# digital_host_for_ADS1216_power.net
KiCad netlist of a schematic drawn in Altium Designer
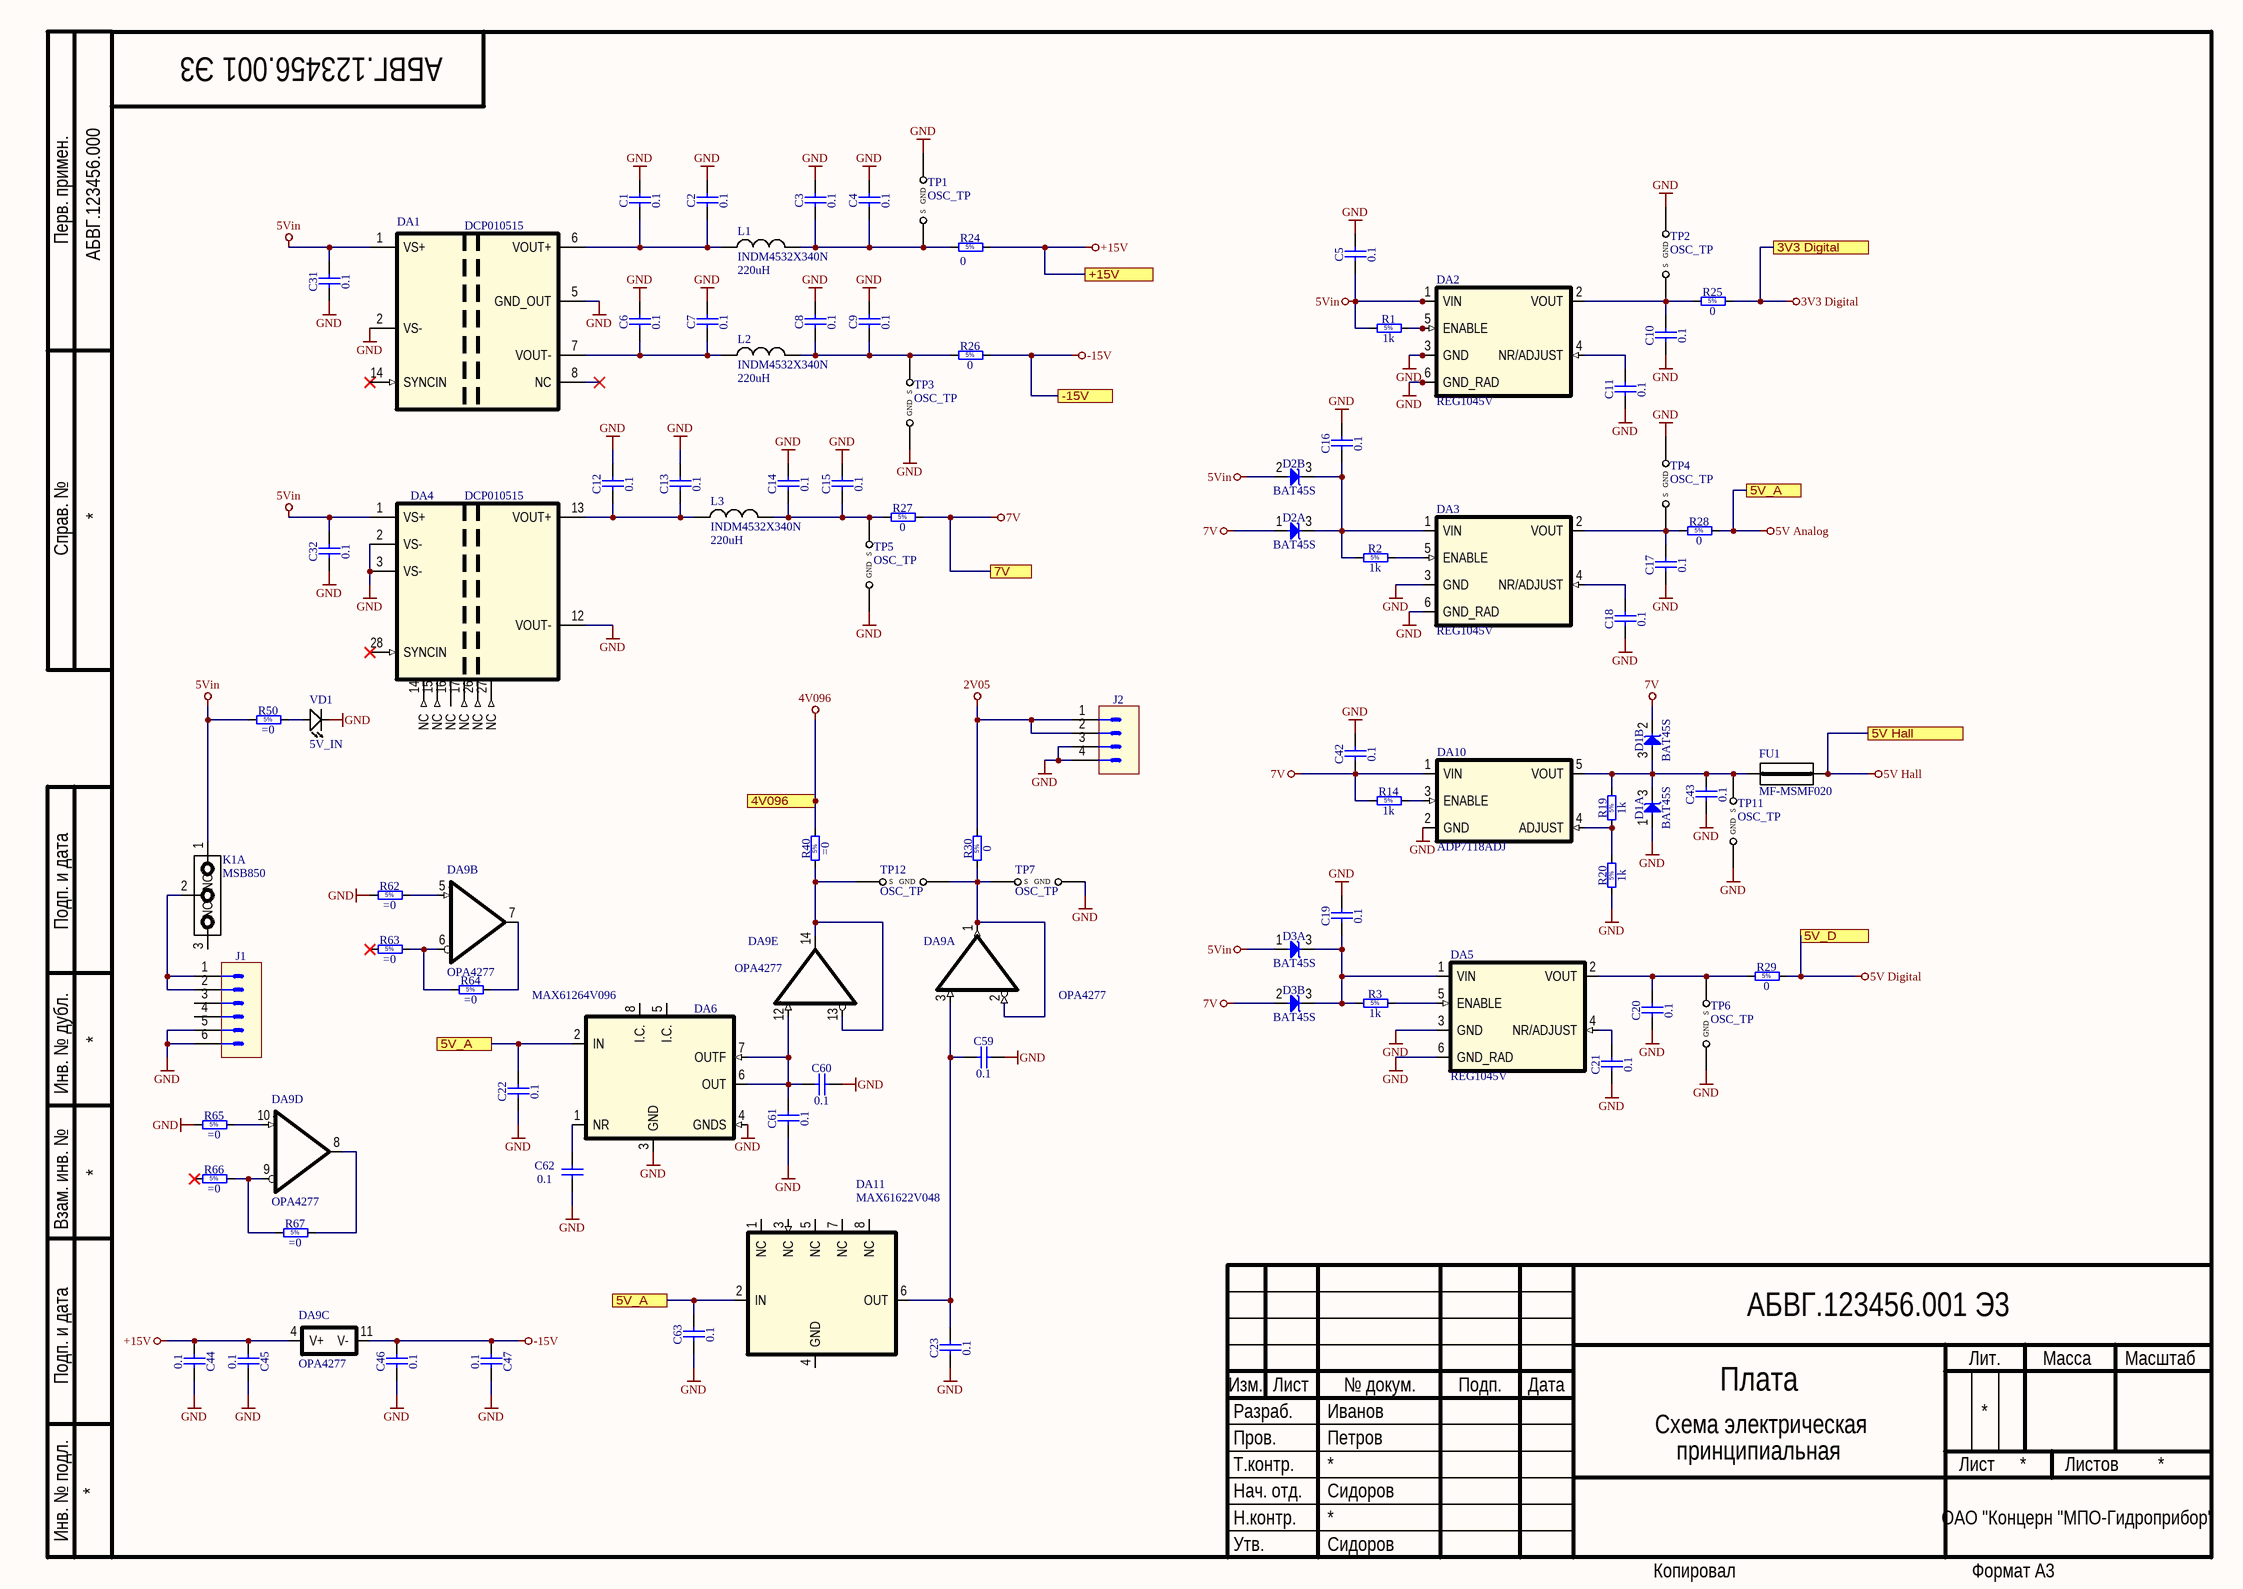
[diagram p0: digital_host_for_ADS1216_power.SchDoc]

(export (version "E")
  (design (tool "Eeschema 10.0.6"))
  (components
    (comp (ref "C1")
      (value "0.1")
      (footprint "CAPC2012X90N")
      (description "Non-polarised capacitor2012")
      (libsource (lib "schematic_hall_library") (part "Capacitor - non polarized"))
    )
    (comp (ref "C2")
      (value "0.1")
      (footprint "CAPC2012X90N")
      (description "Non-polarised capacitor2012")
      (libsource (lib "schematic_hall_library") (part "Capacitor - non polarized"))
    )
    (comp (ref "C3")
      (value "0.1")
      (footprint "CAPC2012X90N")
      (description "Non-polarised capacitor2012")
      (libsource (lib "schematic_hall_library") (part "Capacitor - non polarized"))
    )
    (comp (ref "C4")
      (value "0.1")
      (footprint "CAPC2012X90N")
      (description "Non-polarised capacitor2012")
      (libsource (lib "schematic_hall_library") (part "Capacitor - non polarized"))
    )
    (comp (ref "C5")
      (value "0.1")
      (footprint "CAPC2012X90N")
      (description "Non-polarised capacitor2012")
      (libsource (lib "schematic_hall_library") (part "Capacitor - non polarized"))
    )
    (comp (ref "C6")
      (value "0.1")
      (footprint "CAPC2012X90N")
      (description "Non-polarised capacitor2012")
      (libsource (lib "schematic_hall_library") (part "Capacitor - non polarized"))
    )
    (comp (ref "C7")
      (value "0.1")
      (footprint "CAPC2012X90N")
      (description "Non-polarised capacitor2012")
      (libsource (lib "schematic_hall_library") (part "Capacitor - non polarized"))
    )
    (comp (ref "C8")
      (value "0.1")
      (footprint "CAPC2012X90N")
      (description "Non-polarised capacitor2012")
      (libsource (lib "schematic_hall_library") (part "Capacitor - non polarized"))
    )
    (comp (ref "C9")
      (value "0.1")
      (footprint "CAPC2012X90N")
      (description "Non-polarised capacitor2012")
      (libsource (lib "schematic_hall_library") (part "Capacitor - non polarized"))
    )
    (comp (ref "C10")
      (value "0.1")
      (footprint "CAPC2012X90N")
      (description "Non-polarised capacitor2012")
      (libsource (lib "schematic_hall_library") (part "Capacitor - non polarized"))
    )
    (comp (ref "C11")
      (value "0.1")
      (footprint "CAPC2012X90N")
      (description "Non-polarised capacitor2012")
      (libsource (lib "schematic_hall_library") (part "Capacitor - non polarized"))
    )
    (comp (ref "C12")
      (value "0.1")
      (footprint "CAPC2012X90N")
      (description "Non-polarised capacitor2012")
      (libsource (lib "schematic_hall_library") (part "Capacitor - non polarized"))
    )
    (comp (ref "C13")
      (value "0.1")
      (footprint "CAPC2012X90N")
      (description "Non-polarised capacitor2012")
      (libsource (lib "schematic_hall_library") (part "Capacitor - non polarized"))
    )
    (comp (ref "C14")
      (value "0.1")
      (footprint "CAPC2012X90N")
      (description "Non-polarised capacitor2012")
      (libsource (lib "schematic_hall_library") (part "Capacitor - non polarized"))
    )
    (comp (ref "C15")
      (value "0.1")
      (footprint "CAPC2012X90N")
      (description "Non-polarised capacitor2012")
      (libsource (lib "schematic_hall_library") (part "Capacitor - non polarized"))
    )
    (comp (ref "C16")
      (value "0.1")
      (footprint "CAPC2012X90N")
      (description "Non-polarised capacitor2012")
      (libsource (lib "schematic_hall_library") (part "Capacitor - non polarized"))
    )
    (comp (ref "C17")
      (value "0.1")
      (footprint "CAPC2012X90N")
      (description "Non-polarised capacitor2012")
      (libsource (lib "schematic_hall_library") (part "Capacitor - non polarized"))
    )
    (comp (ref "C18")
      (value "0.1")
      (footprint "CAPC2012X90N")
      (description "Non-polarised capacitor2012")
      (libsource (lib "schematic_hall_library") (part "Capacitor - non polarized"))
    )
    (comp (ref "C19")
      (value "0.1")
      (footprint "CAPC2012X90N")
      (description "Non-polarised capacitor2012")
      (libsource (lib "schematic_hall_library") (part "Capacitor - non polarized"))
    )
    (comp (ref "C20")
      (value "0.1")
      (footprint "CAPC2012X90N")
      (description "Non-polarised capacitor2012")
      (libsource (lib "schematic_hall_library") (part "Capacitor - non polarized"))
    )
    (comp (ref "C21")
      (value "0.1")
      (footprint "CAPC2012X90N")
      (description "Non-polarised capacitor2012")
      (libsource (lib "schematic_hall_library") (part "Capacitor - non polarized"))
    )
    (comp (ref "C22")
      (value "0.1")
      (footprint "CAPC2012X90N")
      (description "Non-polarised capacitor2012")
      (libsource (lib "schematic_hall_library") (part "Capacitor - non polarized"))
    )
    (comp (ref "C23")
      (value "0.1")
      (footprint "CAPC2012X90N")
      (description "Non-polarised capacitor2012")
      (libsource (lib "schematic_hall_library") (part "Capacitor - non polarized"))
    )
    (comp (ref "C31")
      (value "0.1")
      (footprint "CAPC2012X90N")
      (description "Non-polarised capacitor2012")
      (libsource (lib "schematic_hall_library") (part "Capacitor - non polarized"))
    )
    (comp (ref "C32")
      (value "0.1")
      (footprint "CAPC2012X90N")
      (description "Non-polarised capacitor2012")
      (libsource (lib "schematic_hall_library") (part "Capacitor - non polarized"))
    )
    (comp (ref "C42")
      (value "0.1")
      (footprint "CAPC2012X90N")
      (description "Non-polarised capacitor2012")
      (libsource (lib "schematic_hall_library") (part "Capacitor - non polarized"))
    )
    (comp (ref "C43")
      (value "0.1")
      (footprint "CAPC2012X90N")
      (description "Non-polarised capacitor2012")
      (libsource (lib "schematic_hall_library") (part "Capacitor - non polarized"))
    )
    (comp (ref "C44")
      (value "0.1")
      (footprint "CAPC2012X90N")
      (description "Non-polarised capacitor2012")
      (libsource (lib "schematic_hall_library") (part "Capacitor - non polarized"))
    )
    (comp (ref "C45")
      (value "0.1")
      (footprint "CAPC2012X90N")
      (description "Non-polarised capacitor2012")
      (libsource (lib "schematic_hall_library") (part "Capacitor - non polarized"))
    )
    (comp (ref "C46")
      (value "0.1")
      (footprint "CAPC2012X90N")
      (description "Non-polarised capacitor2012")
      (libsource (lib "schematic_hall_library") (part "Capacitor - non polarized"))
    )
    (comp (ref "C47")
      (value "0.1")
      (footprint "CAPC2012X90N")
      (description "Non-polarised capacitor2012")
      (libsource (lib "schematic_hall_library") (part "Capacitor - non polarized"))
    )
    (comp (ref "C59")
      (value "0.1")
      (footprint "CAPC2012X90N")
      (description "Non-polarised capacitor2012")
      (libsource (lib "schematic_hall_library") (part "Capacitor - non polarized"))
    )
    (comp (ref "C60")
      (value "0.1")
      (footprint "CAPC2012X90N")
      (description "Non-polarised capacitor2012")
      (libsource (lib "schematic_hall_library") (part "Capacitor - non polarized"))
    )
    (comp (ref "C61")
      (value "0.1")
      (footprint "CAPC2012X90N")
      (description "Non-polarised capacitor2012")
      (libsource (lib "schematic_hall_library") (part "Capacitor - non polarized"))
    )
    (comp (ref "C62")
      (value "0.1")
      (footprint "CAPC2012X90N")
      (description "Non-polarised capacitor2012")
      (libsource (lib "schematic_hall_library") (part "Capacitor - non polarized"))
    )
    (comp (ref "C63")
      (value "0.1")
      (footprint "CAPC2012X90N")
      (description "Non-polarised capacitor2012")
      (libsource (lib "schematic_hall_library") (part "Capacitor - non polarized"))
    )
    (comp (ref "D1")
      (value "BAT45S")
      (footprint "footprint_library:SOT-23")
      (description "Serial Shottky Diode")
      (libsource (lib "first_scheme.~(65)") (part "BAT54S"))
    )
    (comp (ref "D2")
      (value "BAT45S")
      (footprint "SOT-23")
      (description "Common Cathode 2 Shottky Diode")
      (libsource (lib "Integrated_Library1") (part "BAT54C"))
    )
    (comp (ref "D3")
      (value "BAT45S")
      (footprint "SOT-23")
      (description "Common Cathode 2 Shottky Diode")
      (libsource (lib "Integrated_Library1") (part "BAT54C"))
    )
    (comp (ref "DA1")
      (value "DCP010515")
      (footprint "NVA7")
      (description "DC/DC 5V to isolated +-15V")
      (fields (field (name "COPYRIGHT") "Copyright (C) 2022 Ultra Librarian. All rights reserved."))
      (libsource (lib "Integrated_Library1") (part "DCP020515"))
    )
    (comp (ref "DA2")
      (value "REG1045V")
      (footprint "SOT223_6-127")
      (description "Positive LDO Linear stabilizer 5Vin to 3V3Digital")
      (libsource (lib "first_scheme.~(65)") (part "REG104_5V"))
    )
    (comp (ref "DA3")
      (value "REG1045V")
      (footprint "SOT223_6-127")
      (description "Positive LDO Linear stabilizer 7V to 5V Analog")
      (libsource (lib "first_scheme.~(65)") (part "REG104_5V"))
    )
    (comp (ref "DA4")
      (value "DCP010515")
      (footprint "footprint_library:SOIC127P1033X265-12_28N")
      (description "DC/DC 5V to isolated +-7V")
      (fields (field (name "COPYRIGHT") "Copyright (C) 2022 Ultra Librarian. All rights reserved."))
      (libsource (lib "first_scheme.~(65)") (part "DCP020507U"))
    )
    (comp (ref "DA5")
      (value "REG1045V")
      (footprint "SOT223_6-127")
      (description "Positive LDO Linear stabilizer 7V to 5V Digital")
      (libsource (lib "first_scheme.~(65)") (part "REG104_5V"))
    )
    (comp (ref "DA6")
      (value "MAX61264V096")
      (footprint "SO8")
      (description "Positive LDO Linear stabilizer")
      (libsource (lib "hall library") (part "MAX6126"))
    )
    (comp (ref "DA9")
      (value "OPA4277")
      (footprint "SOIC14")
      (description "счетверённый ОУ")
      (fields (field (name "VOLTAGE") "3..30V/+-1.5..+-15V"))
      (libsource (lib "Integrated_Library1") (part "OPA4277"))
    )
    (comp (ref "DA10")
      (value "ADP7118ADJ")
      (footprint "SOT95P270X145-5N")
      (description "Positive LDO Linear stabilizer")
      (libsource (lib "Integrated_Library1") (part "ADP7118"))
    )
    (comp (ref "DA11")
      (value "MAX61622V048")
      (footprint "SO8")
      (description "Reference LDO Linear stabilizer")
      (libsource (lib "hall library") (part "MAX6162"))
    )
    (comp (ref "FU1")
      (value "MF-MSMF020")
      (footprint "MSMF020")
      (description "Предохранитель самовосстанавливающийся")
      (libsource (lib "Integrated_Library1") (part "MF-MSMF"))
    )
    (comp (ref "J1")
      (value "~")
      (footprint "MOLEX_22-27-2061")
      (description "Connector 4 Male")
      (libsource (lib "hall library") (part "WF6"))
    )
    (comp (ref "J2")
      (value "~")
      (footprint "MOLEX_22-27-2041")
      (description "Connector 4 Male")
      (libsource (lib "hall library") (part "WF4"))
    )
    (comp (ref "K1")
      (value "MSB850")
      (footprint "MSB850")
      (description "Кнопка с фиксацией 2xSPDT")
      (libsource (lib "hall library") (part "MSB850"))
    )
    (comp (ref "L1")
      (value "INDM4532X340N")
      (footprint "footprint_library:INDM4532X340N")
      (description "SMD Дроссель")
      (fields (field (name "INDUCTANCE") "220uH"))
      (libsource (lib "first_scheme.~(65)") (part "INDM4532X340N"))
    )
    (comp (ref "L2")
      (value "INDM4532X340N")
      (footprint "footprint_library:INDM4532X340N")
      (description "SMD Дроссель")
      (fields (field (name "INDUCTANCE") "220uH"))
      (libsource (lib "first_scheme.~(65)") (part "INDM4532X340N"))
    )
    (comp (ref "L3")
      (value "INDM4532X340N")
      (footprint "footprint_library:INDM4532X340N")
      (description "SMD Дроссель")
      (fields (field (name "INDUCTANCE") "220uH"))
      (libsource (lib "first_scheme.~(65)") (part "INDM4532X340N"))
    )
    (comp (ref "R1")
      (value "1k")
      (footprint "RESC2012X70N")
      (description "Resistor - 5%")
      (fields (field (name "TOLERANCE") "5%"))
      (libsource (lib "first_scheme.~(65)") (part "Resistor - 5%"))
    )
    (comp (ref "R2")
      (value "1k")
      (footprint "RESC2012X70N")
      (description "Resistor - 5%")
      (fields (field (name "TOLERANCE") "5%"))
      (libsource (lib "first_scheme.~(65)") (part "Resistor - 5%"))
    )
    (comp (ref "R3")
      (value "1k")
      (footprint "RESC2012X70N")
      (description "Resistor - 5%")
      (fields (field (name "TOLERANCE") "5%"))
      (libsource (lib "first_scheme.~(65)") (part "Resistor - 5%"))
    )
    (comp (ref "R14")
      (value "1k")
      (footprint "RESC2012X70N")
      (description "Resistor - 5%")
      (fields (field (name "TOLERANCE") "5%"))
      (libsource (lib "Integrated_Library1") (part "Resistor - 5%"))
    )
    (comp (ref "R19")
      (value "1k")
      (footprint "RESC2012X70N")
      (description "Resistor - 5%")
      (fields (field (name "TOLERANCE") "5%"))
      (libsource (lib "Integrated_Library1") (part "Resistor - 5%"))
    )
    (comp (ref "R20")
      (value "1k")
      (footprint "RESC2012X70N")
      (description "Resistor - 5%")
      (fields (field (name "TOLERANCE") "5%"))
      (libsource (lib "Integrated_Library1") (part "Resistor - 5%"))
    )
    (comp (ref "R24")
      (value "0")
      (footprint "RESC2012X70N")
      (description "Resistor - 5%")
      (fields (field (name "TOLERANCE") "5%"))
      (libsource (lib "Integrated_Library1") (part "Resistor - 5%"))
    )
    (comp (ref "R25")
      (value "0")
      (footprint "RESC2012X70N")
      (description "Resistor - 5%")
      (fields (field (name "TOLERANCE") "5%"))
      (libsource (lib "Integrated_Library1") (part "Resistor - 5%"))
    )
    (comp (ref "R26")
      (value "0")
      (footprint "RESC2012X70N")
      (description "Resistor - 5%")
      (fields (field (name "TOLERANCE") "5%"))
      (libsource (lib "Integrated_Library1") (part "Resistor - 5%"))
    )
    (comp (ref "R27")
      (value "0")
      (footprint "RESC2012X70N")
      (description "Resistor - 5%")
      (fields (field (name "TOLERANCE") "5%"))
      (libsource (lib "Integrated_Library1") (part "Resistor - 5%"))
    )
    (comp (ref "R28")
      (value "0")
      (footprint "RESC2012X70N")
      (description "Resistor - 5%")
      (fields (field (name "TOLERANCE") "5%"))
      (libsource (lib "Integrated_Library1") (part "Resistor - 5%"))
    )
    (comp (ref "R29")
      (value "0")
      (footprint "RESC2012X70N")
      (description "Resistor - 5%")
      (fields (field (name "TOLERANCE") "5%"))
      (libsource (lib "Integrated_Library1") (part "Resistor - 5%"))
    )
    (comp (ref "R30")
      (value "0")
      (footprint "RESC2012X70N")
      (description "Resistor - 5%")
      (fields (field (name "TOLERANCE") "5%"))
      (libsource (lib "Integrated_Library1") (part "Resistor - 5%"))
    )
    (comp (ref "R40")
      (value "~")
      (footprint "RESC2012X70N")
      (description "Resistor - 5%")
      (fields (field (name "TOLERANCE") "5%"))
      (libsource (lib "Integrated_Library1") (part "Resistor - 5%"))
    )
    (comp (ref "R50")
      (value "~")
      (footprint "RESC2012X70N")
      (description "Resistor - 5%")
      (fields (field (name "TOLERANCE") "5%"))
      (libsource (lib "Integrated_Library1") (part "Resistor - 5%"))
    )
    (comp (ref "R62")
      (value "~")
      (footprint "RESC2012X70N")
      (description "Resistor - 5%")
      (fields (field (name "TOLERANCE") "5%"))
      (libsource (lib "Integrated_Library1") (part "Resistor - 5%"))
    )
    (comp (ref "R63")
      (value "~")
      (footprint "RESC2012X70N")
      (description "Resistor - 5%")
      (fields (field (name "TOLERANCE") "5%"))
      (libsource (lib "Integrated_Library1") (part "Resistor - 5%"))
    )
    (comp (ref "R64")
      (value "~")
      (footprint "RESC2012X70N")
      (description "Resistor - 5%")
      (fields (field (name "TOLERANCE") "5%"))
      (libsource (lib "Integrated_Library1") (part "Resistor - 5%"))
    )
    (comp (ref "R65")
      (value "~")
      (footprint "RESC2012X70N")
      (description "Resistor - 5%")
      (fields (field (name "TOLERANCE") "5%"))
      (libsource (lib "Integrated_Library1") (part "Resistor - 5%"))
    )
    (comp (ref "R66")
      (value "~")
      (footprint "RESC2012X70N")
      (description "Resistor - 5%")
      (fields (field (name "TOLERANCE") "5%"))
      (libsource (lib "Integrated_Library1") (part "Resistor - 5%"))
    )
    (comp (ref "R67")
      (value "~")
      (footprint "RESC2012X70N")
      (description "Resistor - 5%")
      (fields (field (name "TOLERANCE") "5%"))
      (libsource (lib "Integrated_Library1") (part "Resistor - 5%"))
    )
    (comp (ref "TP1")
      (value "OSC_TP")
      (footprint "footprint_library:TP2")
      (description "Контрольная точка для подключения осциллографа короткой землёй")
      (libsource (lib "first_scheme.~(65)") (part "OscTP"))
    )
    (comp (ref "TP2")
      (value "OSC_TP")
      (footprint "footprint_library:TP2")
      (description "Контрольная точка для подключения осциллографа короткой землёй")
      (libsource (lib "first_scheme.~(65)") (part "OscTP"))
    )
    (comp (ref "TP3")
      (value "OSC_TP")
      (footprint "footprint_library:TP2")
      (description "Контрольная точка для подключения осциллографа короткой землёй")
      (libsource (lib "first_scheme.~(65)") (part "OscTP"))
    )
    (comp (ref "TP4")
      (value "OSC_TP")
      (footprint "footprint_library:TP2")
      (description "Контрольная точка для подключения осциллографа короткой землёй")
      (libsource (lib "first_scheme.~(65)") (part "OscTP"))
    )
    (comp (ref "TP5")
      (value "OSC_TP")
      (footprint "footprint_library:TP2")
      (description "Контрольная точка для подключения осциллографа короткой землёй")
      (libsource (lib "first_scheme.~(65)") (part "OscTP"))
    )
    (comp (ref "TP6")
      (value "OSC_TP")
      (footprint "footprint_library:TP2")
      (description "Контрольная точка для подключения осциллографа короткой землёй")
      (libsource (lib "first_scheme.~(65)") (part "OscTP"))
    )
    (comp (ref "TP7")
      (value "OSC_TP")
      (footprint "footprint_library:TP2")
      (description "Контрольная точка для подключения осциллографа короткой землёй")
      (libsource (lib "first_scheme.~(65)") (part "OscTP"))
    )
    (comp (ref "TP11")
      (value "OSC_TP")
      (footprint "TP2")
      (description "Контрольная точка для подключения осциллографа короткой землёй")
      (libsource (lib "Integrated_Library1") (part "OscTP"))
    )
    (comp (ref "TP12")
      (value "OSC_TP")
      (footprint "footprint_library:TP2")
      (description "Контрольная точка для подключения осциллографа короткой землёй")
      (libsource (lib "first_scheme.~(65)") (part "OscTP"))
    )
    (comp (ref "VD1")
      (value "5V_IN")
      (footprint "LED0603")
      (description "Чип светодиод 0603")
      (libsource (lib "hall library") (part "LED0603"))
    )
  )
  (nets
    (net (code "1") (name "+15V") (class "Default")
      (node (ref "C44") (pin "1") (pinfunction "1_1") (pintype "passive"))
      (node (ref "C45") (pin "1") (pinfunction "1_1") (pintype "passive"))
      (node (ref "DA9") (pin "4") (pinfunction "V+_4") (pintype "power_in"))
      (node (ref "R24") (pin "2") (pinfunction "2_2") (pintype "passive"))
    )
    (net (code "2") (name "-15V") (class "Default")
      (node (ref "C46") (pin "2") (pinfunction "2_2") (pintype "passive"))
      (node (ref "C47") (pin "1") (pinfunction "1_1") (pintype "passive"))
      (node (ref "DA9") (pin "11") (pinfunction "V-_11") (pintype "power_in"))
      (node (ref "R26") (pin "2") (pinfunction "2_2") (pintype "passive"))
    )
    (net (code "3") (name "2V05") (class "Default")
      (node (ref "J2") (pin "1") (pinfunction "1_1") (pintype "passive"))
      (node (ref "J2") (pin "2") (pinfunction "2_2") (pintype "passive"))
      (node (ref "R30") (pin "2") (pinfunction "2_2") (pintype "passive"))
    )
    (net (code "4") (name "3V3 Digital") (class "Default")
      (node (ref "R25") (pin "2") (pinfunction "2_2") (pintype "passive"))
    )
    (net (code "5") (name "4V096") (class "Default")
      (node (ref "R40") (pin "2") (pinfunction "2_2") (pintype "passive"))
    )
    (net (code "6") (name "5V Analog") (class "Default")
      (node (ref "C22") (pin "2") (pinfunction "2_2") (pintype "passive"))
      (node (ref "C63") (pin "2") (pinfunction "2_2") (pintype "passive"))
      (node (ref "DA11") (pin "2") (pinfunction "IN_2") (pintype "power_in"))
      (node (ref "DA6") (pin "2") (pinfunction "IN_2") (pintype "power_in"))
      (node (ref "R28") (pin "2") (pinfunction "2_2") (pintype "passive"))
    )
    (net (code "7") (name "5V Digital") (class "Default")
      (node (ref "R29") (pin "2") (pinfunction "2_2") (pintype "passive"))
    )
    (net (code "8") (name "5V Hall") (class "Default")
      (node (ref "FU1") (pin "2") (pinfunction "2_2") (pintype "passive"))
    )
    (net (code "9") (name "5Vin") (class "Default")
      (node (ref "C31") (pin "2") (pinfunction "2_2") (pintype "passive"))
      (node (ref "C32") (pin "2") (pinfunction "2_2") (pintype "passive"))
      (node (ref "C5") (pin "1") (pinfunction "1_1") (pintype "passive"))
      (node (ref "D2") (pin "2") (pinfunction "A_2") (pintype "passive"))
      (node (ref "D3") (pin "1") (pinfunction "A_1") (pintype "passive"))
      (node (ref "DA1") (pin "1") (pinfunction "VS+_1") (pintype "power_in"))
      (node (ref "DA2") (pin "1") (pinfunction "VIN_1") (pintype "power_in"))
      (node (ref "DA4") (pin "1") (pinfunction "VS+_1") (pintype "power_in"))
      (node (ref "K1") (pin "1") (pinfunction "NO_1") (pintype "passive"))
      (node (ref "R1") (pin "1") (pinfunction "1_1") (pintype "passive"))
      (node (ref "R50") (pin "2") (pinfunction "2_2") (pintype "passive"))
    )
    (net (code "10") (name "7V") (class "Default")
      (node (ref "C42") (pin "1") (pinfunction "1_1") (pintype "passive"))
      (node (ref "D1") (pin "2") (pinfunction "COMAC_2") (pintype "passive"))
      (node (ref "D2") (pin "1") (pinfunction "A_1") (pintype "passive"))
      (node (ref "D3") (pin "2") (pinfunction "A_2") (pintype "passive"))
      (node (ref "DA10") (pin "1") (pinfunction "VIN_1") (pintype "power_in"))
      (node (ref "R14") (pin "1") (pinfunction "1_1") (pintype "passive"))
      (node (ref "R27") (pin "2") (pinfunction "2_2") (pintype "passive"))
    )
    (net (code "11") (name "GND") (class "Default")
      (node (ref "C1") (pin "2") (pinfunction "2_2") (pintype "passive"))
      (node (ref "C10") (pin "1") (pinfunction "1_1") (pintype "passive"))
      (node (ref "C11") (pin "1") (pinfunction "1_1") (pintype "passive"))
      (node (ref "C12") (pin "2") (pinfunction "2_2") (pintype "passive"))
      (node (ref "C13") (pin "2") (pinfunction "2_2") (pintype "passive"))
      (node (ref "C14") (pin "2") (pinfunction "2_2") (pintype "passive"))
      (node (ref "C15") (pin "2") (pinfunction "2_2") (pintype "passive"))
      (node (ref "C16") (pin "2") (pinfunction "2_2") (pintype "passive"))
      (node (ref "C17") (pin "1") (pinfunction "1_1") (pintype "passive"))
      (node (ref "C18") (pin "1") (pinfunction "1_1") (pintype "passive"))
      (node (ref "C19") (pin "2") (pinfunction "2_2") (pintype "passive"))
      (node (ref "C2") (pin "2") (pinfunction "2_2") (pintype "passive"))
      (node (ref "C20") (pin "1") (pinfunction "1_1") (pintype "passive"))
      (node (ref "C21") (pin "1") (pinfunction "1_1") (pintype "passive"))
      (node (ref "C22") (pin "1") (pinfunction "1_1") (pintype "passive"))
      (node (ref "C23") (pin "1") (pinfunction "1_1") (pintype "passive"))
      (node (ref "C3") (pin "2") (pinfunction "2_2") (pintype "passive"))
      (node (ref "C31") (pin "1") (pinfunction "1_1") (pintype "passive"))
      (node (ref "C32") (pin "1") (pinfunction "1_1") (pintype "passive"))
      (node (ref "C4") (pin "2") (pinfunction "2_2") (pintype "passive"))
      (node (ref "C42") (pin "2") (pinfunction "2_2") (pintype "passive"))
      (node (ref "C43") (pin "1") (pinfunction "1_1") (pintype "passive"))
      (node (ref "C44") (pin "2") (pinfunction "2_2") (pintype "passive"))
      (node (ref "C45") (pin "2") (pinfunction "2_2") (pintype "passive"))
      (node (ref "C46") (pin "1") (pinfunction "1_1") (pintype "passive"))
      (node (ref "C47") (pin "2") (pinfunction "2_2") (pintype "passive"))
      (node (ref "C5") (pin "2") (pinfunction "2_2") (pintype "passive"))
      (node (ref "C59") (pin "2") (pinfunction "2_2") (pintype "passive"))
      (node (ref "C6") (pin "2") (pinfunction "2_2") (pintype "passive"))
      (node (ref "C60") (pin "2") (pinfunction "2_2") (pintype "passive"))
      (node (ref "C61") (pin "1") (pinfunction "1_1") (pintype "passive"))
      (node (ref "C62") (pin "1") (pinfunction "1_1") (pintype "passive"))
      (node (ref "C63") (pin "1") (pinfunction "1_1") (pintype "passive"))
      (node (ref "C7") (pin "2") (pinfunction "2_2") (pintype "passive"))
      (node (ref "C8") (pin "2") (pinfunction "2_2") (pintype "passive"))
      (node (ref "C9") (pin "2") (pinfunction "2_2") (pintype "passive"))
      (node (ref "D1") (pin "1") (pinfunction "A_1") (pintype "passive"))
      (node (ref "DA1") (pin "2") (pinfunction "VS-_2") (pintype "power_in"))
      (node (ref "DA1") (pin "5") (pinfunction "GND_OUT_5") (pintype "power_in"))
      (node (ref "DA10") (pin "2") (pinfunction "GND_2") (pintype "power_in"))
      (node (ref "DA2") (pin "3") (pinfunction "GND_3") (pintype "power_in"))
      (node (ref "DA2") (pin "6") (pinfunction "GND_RAD_6") (pintype "power_in"))
      (node (ref "DA3") (pin "3") (pinfunction "GND_3") (pintype "power_in"))
      (node (ref "DA3") (pin "6") (pinfunction "GND_RAD_6") (pintype "power_in"))
      (node (ref "DA4") (pin "12") (pinfunction "VOUT-_12") (pintype "power_in"))
      (node (ref "DA4") (pin "2") (pinfunction "VS-_2") (pintype "power_in"))
      (node (ref "DA4") (pin "3") (pinfunction "VS-_3") (pintype "power_in"))
      (node (ref "DA5") (pin "3") (pinfunction "GND_3") (pintype "power_in"))
      (node (ref "DA5") (pin "6") (pinfunction "GND_RAD_6") (pintype "power_in"))
      (node (ref "DA6") (pin "3") (pinfunction "GND_3") (pintype "power_in"))
      (node (ref "DA6") (pin "4") (pinfunction "GNDS_4") (pintype "input"))
      (node (ref "J1") (pin "5") (pinfunction "5_5") (pintype "passive"))
      (node (ref "J1") (pin "6") (pinfunction "6_6") (pintype "passive"))
      (node (ref "J2") (pin "3") (pinfunction "3_3") (pintype "passive"))
      (node (ref "J2") (pin "4") (pinfunction "4_4") (pintype "passive"))
      (node (ref "R20") (pin "1") (pinfunction "1_1") (pintype "passive"))
      (node (ref "R62") (pin "1") (pinfunction "1_1") (pintype "passive"))
      (node (ref "R65") (pin "1") (pinfunction "1_1") (pintype "passive"))
      (node (ref "TP1") (pin "2") (pinfunction "GND_2") (pintype "passive"))
      (node (ref "TP11") (pin "2") (pinfunction "GND_2") (pintype "passive"))
      (node (ref "TP2") (pin "2") (pinfunction "GND_2") (pintype "passive"))
      (node (ref "TP3") (pin "2") (pinfunction "GND_2") (pintype "passive"))
      (node (ref "TP4") (pin "2") (pinfunction "GND_2") (pintype "passive"))
      (node (ref "TP5") (pin "2") (pinfunction "GND_2") (pintype "passive"))
      (node (ref "TP6") (pin "2") (pinfunction "GND_2") (pintype "passive"))
      (node (ref "TP7") (pin "2") (pinfunction "GND_2") (pintype "passive"))
      (node (ref "VD1") (pin "1") (pinfunction "Cathode_1") (pintype "passive"))
    )
    (net (code "12") (name "Net-(D1A-COMAC)") (class "Default")
      (node (ref "C43") (pin "2") (pinfunction "2_2") (pintype "passive"))
      (node (ref "D1") (pin "3") (pinfunction "A_3") (pintype "passive"))
      (node (ref "DA10") (pin "5") (pinfunction "VOUT_5") (pintype "power_in"))
      (node (ref "FU1") (pin "1") (pinfunction "1_1") (pintype "passive"))
      (node (ref "R19") (pin "2") (pinfunction "2_2") (pintype "passive"))
      (node (ref "TP11") (pin "1") (pinfunction "S_1") (pintype "passive"))
    )
    (net (code "13") (name "Net-(D2A-COMAC)") (class "Default")
      (node (ref "C16") (pin "1") (pinfunction "1_1") (pintype "passive"))
      (node (ref "D2") (pin "3") (pinfunction "COMAC_3") (pintype "passive"))
      (node (ref "DA3") (pin "1") (pinfunction "VIN_1") (pintype "power_in"))
      (node (ref "R2") (pin "1") (pinfunction "1_1") (pintype "passive"))
    )
    (net (code "14") (name "Net-(D3A-COMAC)") (class "Default")
      (node (ref "C19") (pin "1") (pinfunction "1_1") (pintype "passive"))
      (node (ref "D3") (pin "3") (pinfunction "COMAC_3") (pintype "passive"))
      (node (ref "DA5") (pin "1") (pinfunction "VIN_1") (pintype "power_in"))
      (node (ref "R3") (pin "1") (pinfunction "1_1") (pintype "passive"))
    )
    (net (code "15") (name "Net-(DA1-VOUT+)") (class "Default")
      (node (ref "C1") (pin "1") (pinfunction "1_1") (pintype "passive"))
      (node (ref "C2") (pin "1") (pinfunction "1_1") (pintype "passive"))
      (node (ref "DA1") (pin "6") (pinfunction "VOUT+_6") (pintype "power_in"))
      (node (ref "L1") (pin "1") (pinfunction "1_1") (pintype "passive"))
    )
    (net (code "16") (name "Net-(DA1-VOUT-)") (class "Default")
      (node (ref "C6") (pin "1") (pinfunction "1_1") (pintype "passive"))
      (node (ref "C7") (pin "1") (pinfunction "1_1") (pintype "passive"))
      (node (ref "DA1") (pin "7") (pinfunction "VOUT-_7") (pintype "power_in"))
      (node (ref "L2") (pin "1") (pinfunction "1_1") (pintype "passive"))
    )
    (net (code "17") (name "Net-(DA2-ENABLE)") (class "Default")
      (node (ref "DA2") (pin "5") (pinfunction "ENABLE_5") (pintype "input"))
      (node (ref "R1") (pin "2") (pinfunction "2_2") (pintype "passive"))
    )
    (net (code "18") (name "Net-(DA2-NR{slash}ADJUST)") (class "Default")
      (node (ref "C11") (pin "2") (pinfunction "2_2") (pintype "passive"))
      (node (ref "DA2") (pin "4") (pinfunction "NR/ADJUST_4") (pintype "input"))
    )
    (net (code "19") (name "Net-(DA2-VOUT)") (class "Default")
      (node (ref "C10") (pin "2") (pinfunction "2_2") (pintype "passive"))
      (node (ref "DA2") (pin "2") (pinfunction "VOUT_2") (pintype "power_in"))
      (node (ref "R25") (pin "1") (pinfunction "1_1") (pintype "passive"))
      (node (ref "TP2") (pin "1") (pinfunction "S_1") (pintype "passive"))
    )
    (net (code "20") (name "Net-(DA3-ENABLE)") (class "Default")
      (node (ref "DA3") (pin "5") (pinfunction "ENABLE_5") (pintype "input"))
      (node (ref "R2") (pin "2") (pinfunction "2_2") (pintype "passive"))
    )
    (net (code "21") (name "Net-(DA3-NR{slash}ADJUST)") (class "Default")
      (node (ref "C18") (pin "2") (pinfunction "2_2") (pintype "passive"))
      (node (ref "DA3") (pin "4") (pinfunction "NR/ADJUST_4") (pintype "input"))
    )
    (net (code "22") (name "Net-(DA3-VOUT)") (class "Default")
      (node (ref "C17") (pin "2") (pinfunction "2_2") (pintype "passive"))
      (node (ref "DA3") (pin "2") (pinfunction "VOUT_2") (pintype "power_in"))
      (node (ref "R28") (pin "1") (pinfunction "1_1") (pintype "passive"))
      (node (ref "TP4") (pin "1") (pinfunction "S_1") (pintype "passive"))
    )
    (net (code "23") (name "Net-(DA4-VOUT+)") (class "Default")
      (node (ref "C12") (pin "1") (pinfunction "1_1") (pintype "passive"))
      (node (ref "C13") (pin "1") (pinfunction "1_1") (pintype "passive"))
      (node (ref "DA4") (pin "13") (pinfunction "VOUT+_13") (pintype "power_in"))
      (node (ref "L3") (pin "1") (pinfunction "1_1") (pintype "passive"))
    )
    (net (code "24") (name "Net-(DA5-ENABLE)") (class "Default")
      (node (ref "DA5") (pin "5") (pinfunction "ENABLE_5") (pintype "input"))
      (node (ref "R3") (pin "2") (pinfunction "2_2") (pintype "passive"))
    )
    (net (code "25") (name "Net-(DA5-NR{slash}ADJUST)") (class "Default")
      (node (ref "C21") (pin "2") (pinfunction "2_2") (pintype "passive"))
      (node (ref "DA5") (pin "4") (pinfunction "NR/ADJUST_4") (pintype "input"))
    )
    (net (code "26") (name "Net-(DA5-VOUT)") (class "Default")
      (node (ref "C20") (pin "2") (pinfunction "2_2") (pintype "passive"))
      (node (ref "DA5") (pin "2") (pinfunction "VOUT_2") (pintype "power_in"))
      (node (ref "R29") (pin "1") (pinfunction "1_1") (pintype "passive"))
      (node (ref "TP6") (pin "1") (pinfunction "S_1") (pintype "passive"))
    )
    (net (code "27") (name "Net-(DA6-NR)") (class "Default")
      (node (ref "C62") (pin "2") (pinfunction "2_2") (pintype "passive"))
      (node (ref "DA6") (pin "1") (pinfunction "NR_1") (pintype "passive"))
    )
    (net (code "28") (name "Net-(DA6-OUT)") (class "Default")
      (node (ref "C60") (pin "1") (pinfunction "1_1") (pintype "passive"))
      (node (ref "C61") (pin "2") (pinfunction "2_2") (pintype "passive"))
      (node (ref "DA6") (pin "6") (pinfunction "OUT_6") (pintype "power_in"))
      (node (ref "DA6") (pin "7") (pinfunction "OUTF_7") (pintype "input"))
      (node (ref "DA9") (pin "12") (pinfunction "+_12") (pintype "input"))
    )
    (net (code "29") (name "Net-(DA9A--)") (class "Default")
      (node (ref "DA9") (pin "1") (pinfunction "OUT_1") (pintype "output"))
      (node (ref "DA9") (pin "2") (pinfunction "-_2") (pintype "input"))
      (node (ref "R30") (pin "1") (pinfunction "1_1") (pintype "passive"))
      (node (ref "TP12") (pin "2") (pinfunction "GND_2") (pintype "passive"))
      (node (ref "TP7") (pin "1") (pinfunction "S_1") (pintype "passive"))
    )
    (net (code "30") (name "Net-(DA9B-+)") (class "Default")
      (node (ref "DA9") (pin "5") (pinfunction "+_5") (pintype "input"))
      (node (ref "R62") (pin "2") (pinfunction "2_2") (pintype "passive"))
    )
    (net (code "31") (name "Net-(DA9B--)") (class "Default")
      (node (ref "DA9") (pin "6") (pinfunction "-_6") (pintype "passive"))
      (node (ref "R63") (pin "2") (pinfunction "2_2") (pintype "passive"))
      (node (ref "R64") (pin "1") (pinfunction "1_1") (pintype "passive"))
    )
    (net (code "32") (name "Net-(DA9B-OUT)") (class "Default")
      (node (ref "DA9") (pin "7") (pinfunction "OUT_7") (pintype "passive"))
      (node (ref "R64") (pin "2") (pinfunction "2_2") (pintype "passive"))
    )
    (net (code "33") (name "Net-(DA9D-+)") (class "Default")
      (node (ref "DA9") (pin "10") (pinfunction "+_10") (pintype "input"))
      (node (ref "R65") (pin "2") (pinfunction "2_2") (pintype "passive"))
    )
    (net (code "34") (name "Net-(DA9D--)") (class "Default")
      (node (ref "DA9") (pin "9") (pinfunction "-_9") (pintype "passive"))
      (node (ref "R66") (pin "2") (pinfunction "2_2") (pintype "passive"))
      (node (ref "R67") (pin "1") (pinfunction "1_1") (pintype "passive"))
    )
    (net (code "35") (name "Net-(DA9D-OUT)") (class "Default")
      (node (ref "DA9") (pin "8") (pinfunction "OUT_8") (pintype "passive"))
      (node (ref "R67") (pin "2") (pinfunction "2_2") (pintype "passive"))
    )
    (net (code "36") (name "Net-(DA9E--)") (class "Default")
      (node (ref "DA9") (pin "13") (pinfunction "-_13") (pintype "passive"))
      (node (ref "DA9") (pin "14") (pinfunction "OUT_14") (pintype "passive"))
      (node (ref "R40") (pin "1") (pinfunction "1_1") (pintype "passive"))
      (node (ref "TP12") (pin "1") (pinfunction "S_1") (pintype "passive"))
    )
    (net (code "37") (name "Net-(DA10-ADJUST)") (class "Default")
      (node (ref "DA10") (pin "4") (pinfunction "ADJUST_4") (pintype "input"))
      (node (ref "R19") (pin "1") (pinfunction "1_1") (pintype "passive"))
      (node (ref "R20") (pin "2") (pinfunction "2_2") (pintype "passive"))
    )
    (net (code "38") (name "Net-(DA10-ENABLE)") (class "Default")
      (node (ref "DA10") (pin "3") (pinfunction "ENABLE_3") (pintype "input"))
      (node (ref "R14") (pin "2") (pinfunction "2_2") (pintype "passive"))
    )
    (net (code "39") (name "Net-(DA11-OUT)") (class "Default")
      (node (ref "C23") (pin "2") (pinfunction "2_2") (pintype "passive"))
      (node (ref "C59") (pin "1") (pinfunction "1_1") (pintype "passive"))
      (node (ref "DA11") (pin "6") (pinfunction "OUT_6") (pintype "power_in"))
      (node (ref "DA9") (pin "3") (pinfunction "+_3") (pintype "input"))
    )
    (net (code "40") (name "Net-(K1A-Cetnter)") (class "Default")
      (node (ref "J1") (pin "1") (pinfunction "1_1") (pintype "passive"))
      (node (ref "J1") (pin "2") (pinfunction "2_2") (pintype "passive"))
      (node (ref "K1") (pin "2") (pinfunction "Cetnter_2") (pintype "passive"))
    )
    (net (code "41") (name "Net-(TP1-S)") (class "Default")
      (node (ref "C3") (pin "1") (pinfunction "1_1") (pintype "passive"))
      (node (ref "C4") (pin "1") (pinfunction "1_1") (pintype "passive"))
      (node (ref "L1") (pin "2") (pinfunction "2_2") (pintype "passive"))
      (node (ref "R24") (pin "1") (pinfunction "1_1") (pintype "passive"))
      (node (ref "TP1") (pin "1") (pinfunction "S_1") (pintype "passive"))
    )
    (net (code "42") (name "Net-(TP3-S)") (class "Default")
      (node (ref "C8") (pin "1") (pinfunction "1_1") (pintype "passive"))
      (node (ref "C9") (pin "1") (pinfunction "1_1") (pintype "passive"))
      (node (ref "L2") (pin "2") (pinfunction "2_2") (pintype "passive"))
      (node (ref "R26") (pin "1") (pinfunction "1_1") (pintype "passive"))
      (node (ref "TP3") (pin "1") (pinfunction "S_1") (pintype "passive"))
    )
    (net (code "43") (name "Net-(TP5-S)") (class "Default")
      (node (ref "C14") (pin "1") (pinfunction "1_1") (pintype "passive"))
      (node (ref "C15") (pin "1") (pinfunction "1_1") (pintype "passive"))
      (node (ref "L3") (pin "2") (pinfunction "2_2") (pintype "passive"))
      (node (ref "R27") (pin "1") (pinfunction "1_1") (pintype "passive"))
      (node (ref "TP5") (pin "1") (pinfunction "S_1") (pintype "passive"))
    )
    (net (code "44") (name "Net-(VD1-Anode)") (class "Default")
      (node (ref "R50") (pin "1") (pinfunction "1_1") (pintype "passive"))
      (node (ref "VD1") (pin "2") (pinfunction "Anode_2") (pintype "passive"))
    )
    (net (code "45") (name "unconnected-(DA1-NC-Pad8)") (class "Default")
      (node (ref "DA1") (pin "8") (pinfunction "NC_8") (pintype "passive+no_connect"))
    )
    (net (code "46") (name "unconnected-(DA1-SYNCIN-Pad14)") (class "Default")
      (node (ref "DA1") (pin "14") (pinfunction "SYNCIN_14") (pintype "input+no_connect"))
    )
    (net (code "47") (name "unconnected-(DA4-NC-Pad14)") (class "Default")
      (node (ref "DA4") (pin "14") (pinfunction "NC_14") (pintype "output"))
    )
    (net (code "48") (name "unconnected-(DA4-NC-Pad15)") (class "Default")
      (node (ref "DA4") (pin "15") (pinfunction "NC_15") (pintype "output"))
    )
    (net (code "49") (name "unconnected-(DA4-NC-Pad16)") (class "Default")
      (node (ref "DA4") (pin "16") (pinfunction "NC_16") (pintype "passive"))
    )
    (net (code "50") (name "unconnected-(DA4-NC-Pad17)") (class "Default")
      (node (ref "DA4") (pin "17") (pinfunction "NC_17") (pintype "output"))
    )
    (net (code "51") (name "unconnected-(DA4-NC-Pad26)") (class "Default")
      (node (ref "DA4") (pin "26") (pinfunction "NC_26") (pintype "output"))
    )
    (net (code "52") (name "unconnected-(DA4-NC-Pad27)") (class "Default")
      (node (ref "DA4") (pin "27") (pinfunction "NC_27") (pintype "output"))
    )
    (net (code "53") (name "unconnected-(DA4-SYNCIN-Pad28)") (class "Default")
      (node (ref "DA4") (pin "28") (pinfunction "SYNCIN_28") (pintype "input+no_connect"))
    )
    (net (code "54") (name "unconnected-(DA6-I.C.-Pad5)") (class "Default")
      (node (ref "DA6") (pin "5") (pinfunction "I.C._5") (pintype "passive"))
    )
    (net (code "55") (name "unconnected-(DA6-I.C.-Pad8)") (class "Default")
      (node (ref "DA6") (pin "8") (pinfunction "I.C._8") (pintype "passive"))
    )
    (net (code "56") (name "unconnected-(DA11-GND-Pad4)") (class "Default")
      (node (ref "DA11") (pin "4") (pinfunction "GND_4") (pintype "power_in"))
    )
    (net (code "57") (name "unconnected-(DA11-NC-Pad1)") (class "Default")
      (node (ref "DA11") (pin "1") (pinfunction "NC_1") (pintype "passive"))
    )
    (net (code "58") (name "unconnected-(DA11-NC-Pad3)") (class "Default")
      (node (ref "DA11") (pin "3") (pinfunction "NC_3") (pintype "input"))
    )
    (net (code "59") (name "unconnected-(DA11-NC-Pad5)") (class "Default")
      (node (ref "DA11") (pin "5") (pinfunction "NC_5") (pintype "passive"))
    )
    (net (code "60") (name "unconnected-(DA11-NC-Pad7)") (class "Default")
      (node (ref "DA11") (pin "7") (pinfunction "NC_7") (pintype "passive"))
    )
    (net (code "61") (name "unconnected-(DA11-NC-Pad8)") (class "Default")
      (node (ref "DA11") (pin "8") (pinfunction "NC_8") (pintype "passive"))
    )
    (net (code "62") (name "unconnected-(J1-Pad3)") (class "Default")
      (node (ref "J1") (pin "3") (pinfunction "3_3") (pintype "passive"))
    )
    (net (code "63") (name "unconnected-(J1-Pad4)") (class "Default")
      (node (ref "J1") (pin "4") (pinfunction "4_4") (pintype "passive"))
    )
    (net (code "64") (name "unconnected-(K1A-NC-Pad3)") (class "Default")
      (node (ref "K1") (pin "3") (pinfunction "NC_3") (pintype "passive"))
    )
    (net (code "65") (name "unconnected-(R63-Pad1)") (class "Default")
      (node (ref "R63") (pin "1") (pinfunction "1_1") (pintype "passive+no_connect"))
    )
    (net (code "66") (name "unconnected-(R66-Pad1)") (class "Default")
      (node (ref "R66") (pin "1") (pinfunction "1_1") (pintype "passive+no_connect"))
    )
  )
)
